# M_microcontrolador.net
KiCad netlist of a schematic drawn in Altium Designer
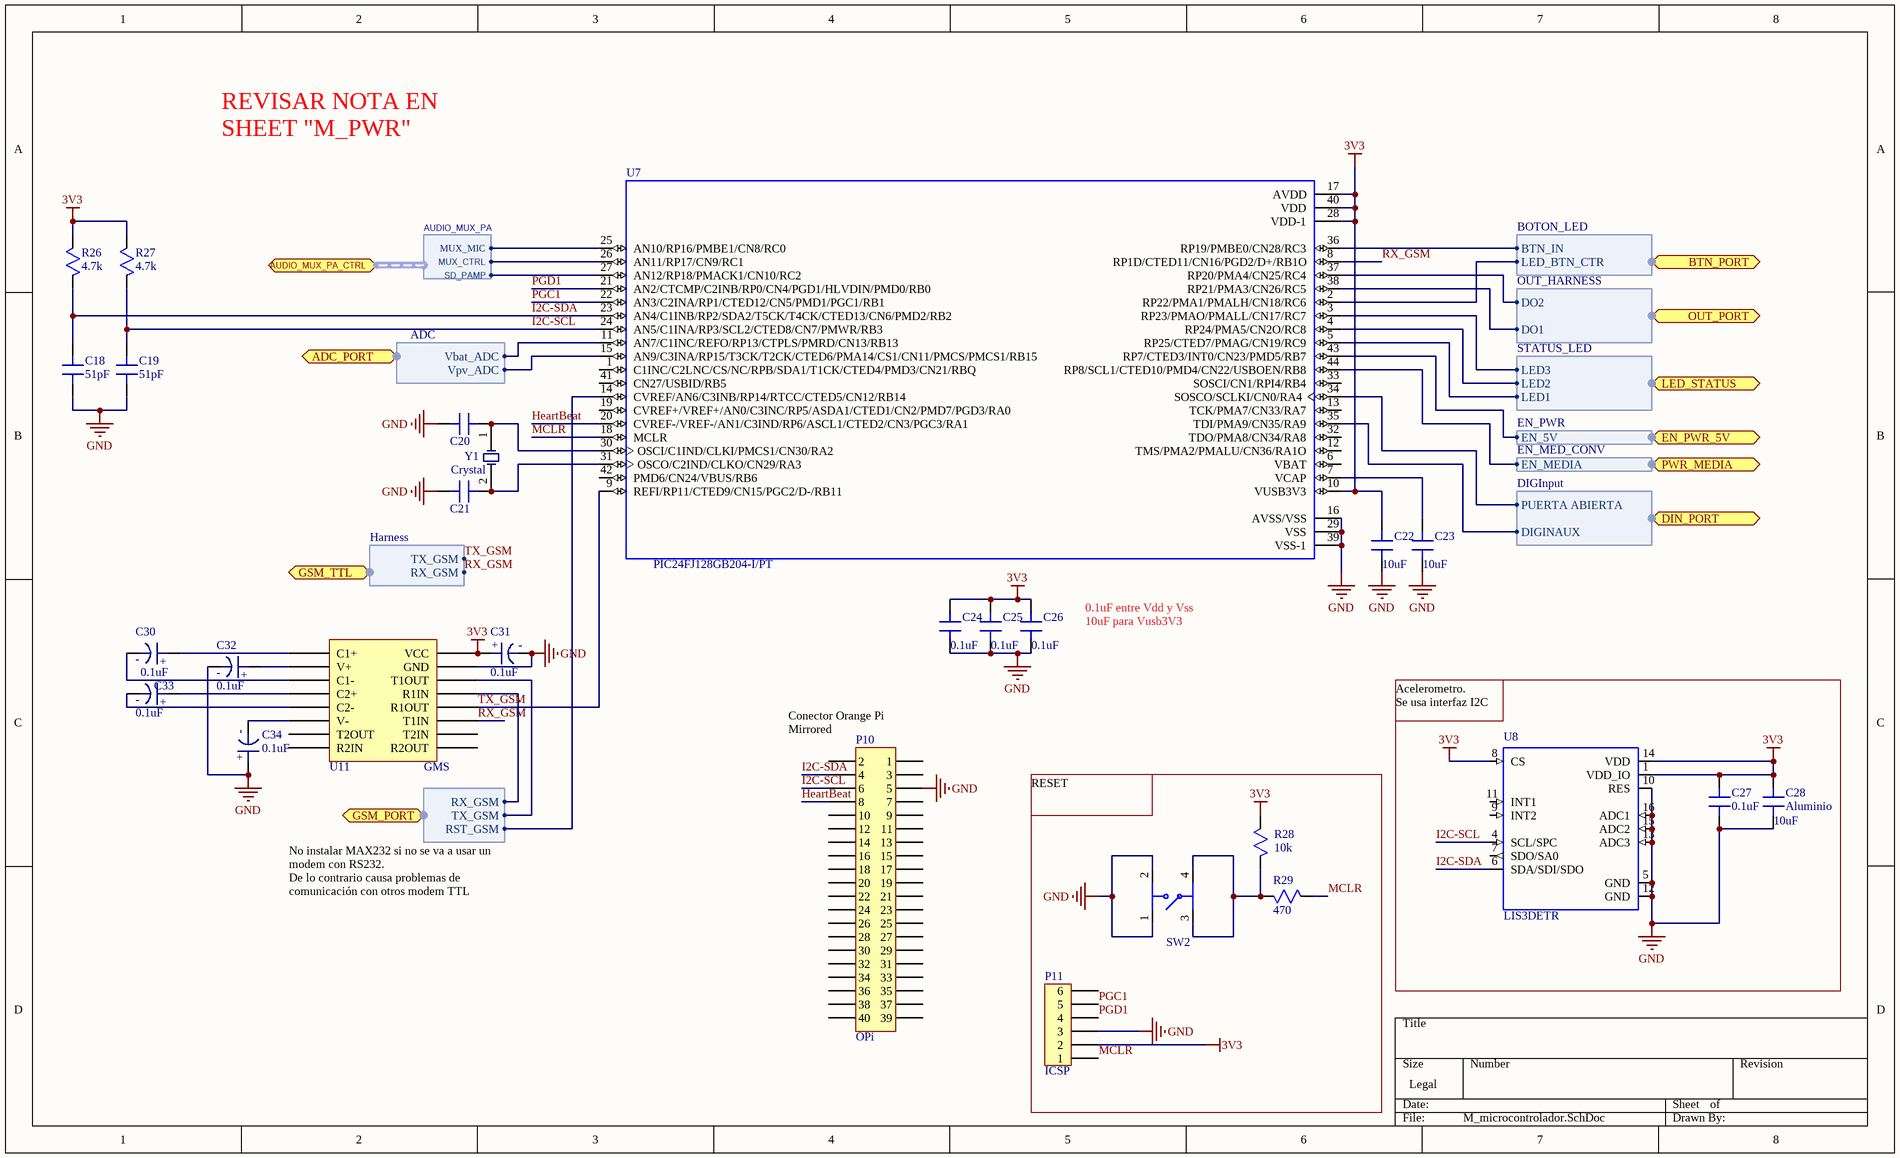
[diagram p0: M_microcontrolador.SchDoc]

(export (version "E")
  (design (tool "Eeschema 10.0.6"))
  (components
    (comp (ref "C18")
      (value "51pF")
      (footprint "Capacitor0805")
      (description "Ceramic Capacitor")
      (fields
        (field (name "DIGI-KEY PART NUMBER") "1276-2670-1-ND")
        (field (name "PARTNO") "CL21C510JBANNNC")
      )
      (libsource (lib "PAT_Library") (part "CapacitorSMD"))
    )
    (comp (ref "C19")
      (value "51pF")
      (footprint "Capacitor0805")
      (description "Ceramic Capacitor")
      (fields
        (field (name "DIGI-KEY PART NUMBER") "1276-2670-1-ND")
        (field (name "PARTNO") "CL21C510JBANNNC")
      )
      (libsource (lib "PAT_Library") (part "CapacitorSMD"))
    )
    (comp (ref "C20")
      (value "CapacitorSMD")
      (footprint "Capacitor0805")
      (description "Ceramic Capacitor")
      (fields (field (name "DIGI-KEY PART NUMBER") "478-10411-1-ND") (field (name "PARTNO") "08051A6R0CAT2A"))
      (libsource (lib "PAT_Library") (part "CapacitorSMD"))
    )
    (comp (ref "C21")
      (value "CapacitorSMD")
      (footprint "Capacitor0805")
      (description "Ceramic Capacitor")
      (fields (field (name "DIGI-KEY PART NUMBER") "478-10411-1-ND") (field (name "PARTNO") "08051A6R0CAT2A"))
      (libsource (lib "PAT_Library") (part "CapacitorSMD"))
    )
    (comp (ref "C22")
      (value "10uF")
      (footprint "Capacitor0805")
      (description "Ceramic Capacitor")
      (fields
        (field (name "DIGI-KEY PART NUMBER") "311-1355-1-ND")
        (field (name "PARTNO") "CC0805ZKY5V6BB106")
      )
      (libsource (lib "ComponentesTruffaV2") (part "CapacitorSMD"))
    )
    (comp (ref "C23")
      (value "10uF")
      (footprint "Capacitor0805")
      (description "Ceramic Capacitor")
      (fields
        (field (name "DIGI-KEY PART NUMBER") "311-1355-1-ND")
        (field (name "PARTNO") "CC0805ZKY5V6BB106")
      )
      (libsource (lib "ComponentesTruffaV2") (part "CapacitorSMD"))
    )
    (comp (ref "C24")
      (value "0.1uF")
      (footprint "Capacitor0805")
      (description "Ceramic Capacitor")
      (fields
        (field (name "DIGI-KEY PART NUMBER") "311-1141-1-ND")
        (field (name "PARTNO") "CC0805KRX7R8BB104")
      )
      (libsource (lib "ComponentesTruffaV2") (part "CapacitorSMD"))
    )
    (comp (ref "C25")
      (value "0.1uF")
      (footprint "Capacitor0805")
      (description "Ceramic Capacitor")
      (fields
        (field (name "DIGI-KEY PART NUMBER") "311-1141-1-ND")
        (field (name "PARTNO") "CC0805KRX7R8BB104")
      )
      (libsource (lib "ComponentesTruffaV2") (part "CapacitorSMD"))
    )
    (comp (ref "C26")
      (value "0.1uF")
      (footprint "Capacitor0805")
      (description "Ceramic Capacitor")
      (fields
        (field (name "DIGI-KEY PART NUMBER") "311-1141-1-ND")
        (field (name "PARTNO") "CC0805KRX7R8BB104")
      )
      (libsource (lib "ComponentesTruffaV2") (part "CapacitorSMD"))
    )
    (comp (ref "C27")
      (value "0.1uF")
      (footprint "Capacitor0805")
      (description "Ceramic Capacitor")
      (fields
        (field (name "DIGI-KEY PART NUMBER") "311-1141-1-ND")
        (field (name "PARTNO") "CC0805KRX7R8BB104")
      )
      (libsource (lib "ComponentesTruffaV2") (part "CapacitorSMD"))
    )
    (comp (ref "C28")
      (value "Aluminio")
      (footprint "Capacitor0805")
      (description "Ceramic Capacitor")
      (fields
        (field (name "ALTIUM_VALUE") "10uF")
        (field (name "DIGI-KEY PART NUMBER") "311-1355-1-ND")
        (field (name "PARTNO") "CC0805ZKY5V6BB106")
      )
      (libsource (lib "ComponentesTruffaV2") (part "CapacitorSMD"))
    )
    (comp (ref "C30")
      (value "0.1uF")
      (footprint "CAPACITORE0805")
      (description "Electrolitic Capacitor")
      (fields
        (field (name "DIGI-KEY PART NUMBER") "311-1141-1-ND")
        (field (name "PARTNO") "CC0805KRX7R8BB104")
      )
      (libsource (lib "PAT_Library") (part "CapacitorESMD"))
    )
    (comp (ref "C31")
      (value "0.1uF")
      (footprint "CAPACITORE0805")
      (description "Electrolitic Capacitor")
      (fields
        (field (name "DIGI-KEY PART NUMBER") "311-1141-1-ND")
        (field (name "PARTNO") "CC0805KRX7R8BB104")
      )
      (libsource (lib "PAT_Library") (part "CapacitorESMD"))
    )
    (comp (ref "C32")
      (value "0.1uF")
      (footprint "CAPACITORE0805")
      (description "Electrolitic Capacitor")
      (fields
        (field (name "DIGI-KEY PART NUMBER") "311-1141-1-ND")
        (field (name "PARTNO") "CC0805KRX7R8BB104")
      )
      (libsource (lib "PAT_Library") (part "CapacitorESMD"))
    )
    (comp (ref "C33")
      (value "0.1uF")
      (footprint "CAPACITORE0805")
      (description "Electrolitic Capacitor")
      (fields
        (field (name "DIGI-KEY PART NUMBER") "311-1141-1-ND")
        (field (name "PARTNO") "CC0805KRX7R8BB104")
      )
      (libsource (lib "PAT_Library") (part "CapacitorESMD"))
    )
    (comp (ref "C34")
      (value "0.1uF")
      (footprint "CAPACITORE0805")
      (description "Electrolitic Capacitor")
      (fields
        (field (name "DIGI-KEY PART NUMBER") "311-1141-1-ND")
        (field (name "PARTNO") "CC0805KRX7R8BB104")
      )
      (libsource (lib "") (part "CapacitorESMD_1"))
    )
    (comp (ref "P10")
      (value "OPi")
      (footprint "MALE2x20PIN")
      (description "Pin Header Male 40 Pins Pitch 2.54mm")
      (fields
        (field (name "DIGI-KEY PART NUMBER") "S7123-ND")
        (field (name "PARTNO") "CONN HDR 40POS 0.1 GOLD PCB")
      )
      (libsource (lib "PAT Connectors Board") (part "PHM2x20P2.54"))
    )
    (comp (ref "P11")
      (value "ICSP")
      (footprint "MALE6PIN")
      (description "Pin Header Male 6 Pins Pitch 2.54mm")
      (fields
        (field (name "DIGI-KEY PART NUMBER") "952-2247-ND")
        (field (name "PARTNO") "CONN HEADER R/A 6POS 2.54MM")
      )
      (libsource (lib "PAT Connectors Board") (part "PHM1x6P2.54"))
    )
    (comp (ref "R26")
      (value "4.7k")
      (footprint "ResistorSMD0805")
      (description "Chip Resistor SMD")
      (fields
        (field (name "DIGI-KEY PART NUMBER") "P4.7KACT-ND")
        (field (name "MANUFACTURERS PART NUMBER") "ERJ-6GEYJ472V")
      )
      (libsource (lib "PAT_Library") (part "ResistorSMD"))
    )
    (comp (ref "R27")
      (value "4.7k")
      (footprint "ResistorSMD0805")
      (description "Chip Resistor SMD")
      (fields
        (field (name "DIGI-KEY PART NUMBER") "P4.7KACT-ND")
        (field (name "MANUFACTURERS PART NUMBER") "ERJ-6GEYJ472V")
      )
      (libsource (lib "PAT_Library") (part "ResistorSMD"))
    )
    (comp (ref "R28")
      (value "10k")
      (footprint "ResistorSMD0805")
      (description "Chip Resistor SMD")
      (fields
        (field (name "DIGI-KEY PART NUMBER") "311-10KARCT-ND")
        (field (name "MANUFACTURERS PART NUMBER") "RC0805JR-0710KL")
      )
      (libsource (lib "PAT_Library") (part "ResistorSMD"))
    )
    (comp (ref "R29")
      (value "470")
      (footprint "ResistorSMD1206")
      (description "Chip Resistor SMD")
      (fields
        (field (name "DIGI-KEY PART NUMBER") "1276-5903-1-ND")
        (field (name "MANUFACTURERS PART NUMBER") "RC3216J471CS")
      )
      (libsource (lib "PAT_Library") (part "ResistorSMD"))
    )
    (comp (ref "SW2")
      (value "Tactile Switch")
      (footprint "TactileSwitch")
      (description "Switch Contact")
      (fields
        (field (name "DIGI-KEY PART NUMBER") "CKN9112CT-ND")
        (field (name "MANUFACTURERS PART NUMBER") "PTS645SM43SMTR92 LFS")
      )
      (libsource (lib "PAT_Library") (part "Tactile Switch"))
    )
    (comp (ref "U7")
      (value "PIC24FJ128GB204-I/PT")
      (footprint "QFP80P1200X1200X120-44N")
      (description "128KB Flash, 8KB RAM, 16 MIPS, USB OTG, Crypto, 44 TQFP 10x10x1mm TRAY")
      (fields (field (name "DIGI-KEY PART NUMBER") "PIC24FJ128GB204-I/PT-ND"))
      (libsource (lib "PIC24FJ128GB204-I_PT") (part "PIC24FJ128GB204-I/PT"))
    )
    (comp (ref "U8")
      (value "LIS3DETR")
      (footprint "LGA16R50P5X3_300X300X100N")
      (description "MEMS digital output motion sensor ultra low-power high performance 3-axes nano accelerometer")
      (fields (field (name "DIGI-KEY PART NUMBER") "497-16262-1-ND"))
      (libsource (lib "LIS3DETR") (part "LIS3DETR"))
    )
    (comp (ref "U11")
      (value "SP3232EBCN")
      (footprint "SP3232EBCN")
      (description "Serial Adapter RS232")
      (fields
        (field (name "DIGI-KEY PART NUMBER") "1016-1803-1-ND")
        (field (name "MANUFACTURERS PART NUMBER") "SP3232ECN-L/TR")
      )
      (libsource (lib "PAT_Library") (part "SP3232EBCN"))
    )
    (comp (ref "Y1")
      (value "Crystal")
      (footprint "CRYSTALSMDMini")
      (description "Crystal SMD")
      (fields
        (field (name "DIGI-KEY PART NUMBER") "XC1842CT-ND")
        (field (name "MANUFACTURERS PART NUMBER") "ECS-240-8-30B-CKM")
      )
      (libsource (lib "PAT_Library") (part "Crystal"))
    )
  )
  (nets
    (net (code "11") (name "/BTN_IN") (class "Default")
      (node (ref "U7") (pin "36") (pinfunction "RP19/PMBE0/CN28/RC3_36") (pintype "bidirectional"))
    )
    (net (code "12") (name "/DIGINAUX") (class "Default")
      (node (ref "U7") (pin "35") (pinfunction "TDI/PMA9/CN35/RA9_35") (pintype "bidirectional"))
    )
    (net (code "13") (name "/DO1") (class "Default")
      (node (ref "U7") (pin "38") (pinfunction "RP21/PMA3/CN26/RC5_38") (pintype "bidirectional"))
    )
    (net (code "14") (name "/DO2") (class "Default")
      (node (ref "U7") (pin "37") (pinfunction "RP20/PMA4/CN25/RC4_37") (pintype "bidirectional"))
    )
    (net (code "15") (name "/EN_5V") (class "Default")
      (node (ref "U7") (pin "43") (pinfunction "RP7/CTED3/INT0/CN23/PMD5/RB7_43") (pintype "bidirectional"))
    )
    (net (code "16") (name "/EN_MEDIA") (class "Default")
      (node (ref "U7") (pin "44") (pinfunction "RP8/SCL1/CTED10/PMD4/CN22/USBOEN/RB8_44") (pintype "bidirectional"))
    )
    (net (code "17") (name "/HeartBeat") (class "Default")
      (node (ref "P10") (pin "8") (pinfunction "8_8") (pintype "passive"))
      (node (ref "U7") (pin "20") (pinfunction "CVREF-/VREF-/AN1/C3IND/RP6/ASCL1/CTED2/CN3/PGC3/RA1_20") (pintype "bidirectional"))
    )
    (net (code "18") (name "/I2C-SCL") (class "Default")
      (node (ref "C19") (pin "1") (pinfunction "1_1") (pintype "passive"))
      (node (ref "P10") (pin "6") (pinfunction "6_6") (pintype "passive"))
      (node (ref "R27") (pin "1") (pinfunction "1_1") (pintype "passive"))
      (node (ref "U7") (pin "24") (pinfunction "AN5/C1INA/RP3/SCL2/CTED8/CN7/PMWR/RB3_24") (pintype "bidirectional"))
      (node (ref "U8") (pin "4") (pinfunction "SCL/SPC_4") (pintype "input"))
    )
    (net (code "19") (name "/I2C-SDA") (class "Default")
      (node (ref "C18") (pin "1") (pinfunction "1_1") (pintype "passive"))
      (node (ref "P10") (pin "4") (pinfunction "4_4") (pintype "passive"))
      (node (ref "R26") (pin "1") (pinfunction "1_1") (pintype "passive"))
      (node (ref "U7") (pin "23") (pinfunction "AN4/C1INB/RP2/SDA2/T5CK/T4CK/CTED13/CN6/PMD2/RB2_23") (pintype "bidirectional"))
      (node (ref "U8") (pin "6") (pinfunction "SDA/SDI/SDO_6") (pintype "bidirectional"))
    )
    (net (code "20") (name "/LED1") (class "Default")
      (node (ref "U7") (pin "5") (pinfunction "RP25/CTED7/PMAG/CN19/RC9_5") (pintype "bidirectional"))
    )
    (net (code "21") (name "/LED2") (class "Default")
      (node (ref "U7") (pin "4") (pinfunction "RP24/PMA5/CN2O/RC8_4") (pintype "bidirectional"))
    )
    (net (code "22") (name "/LED3") (class "Default")
      (node (ref "U7") (pin "3") (pinfunction "RP23/PMAO/PMALL/CN17/RC7_3") (pintype "bidirectional"))
    )
    (net (code "23") (name "/LED_BTN_CTR") (class "Default")
      (node (ref "U7") (pin "2") (pinfunction "RP22/PMA1/PMALH/CN18/RC6_2") (pintype "bidirectional"))
    )
    (net (code "24") (name "/MCLR") (class "Default")
      (node (ref "P11") (pin "1") (pinfunction "1_1") (pintype "passive"))
      (node (ref "R29") (pin "2") (pinfunction "2_2") (pintype "passive"))
      (node (ref "U7") (pin "18") (pinfunction "MCLR_18") (pintype "bidirectional"))
    )
    (net (code "25") (name "/MUX_CTRL") (class "Default")
      (node (ref "U7") (pin "26") (pinfunction "AN11/RP17/CN9/RC1_26") (pintype "bidirectional"))
    )
    (net (code "26") (name "/MUX_MIC") (class "Default")
      (node (ref "U7") (pin "25") (pinfunction "AN10/RP16/PMBE1/CN8/RC0_25") (pintype "bidirectional"))
    )
    (net (code "27") (name "/PGC1") (class "Default")
      (node (ref "P11") (pin "5") (pinfunction "5_5") (pintype "passive"))
      (node (ref "U7") (pin "22") (pinfunction "AN3/C2INA/RP1/CTED12/CN5/PMD1/PGC1/RB1_22") (pintype "bidirectional"))
    )
    (net (code "28") (name "/PGD1") (class "Default")
      (node (ref "P11") (pin "4") (pinfunction "4_4") (pintype "passive"))
      (node (ref "U7") (pin "21") (pinfunction "AN2/CTCMP/C2INB/RP0/CN4/PGD1/HLVDIN/PMD0/RB0_21") (pintype "bidirectional"))
    )
    (net (code "29") (name "/PUERTA ABIERTA") (class "Default")
      (node (ref "U7") (pin "34") (pinfunction "SOSCO/SCLKI/CN0/RA4_34") (pintype "bidirectional"))
    )
    (net (code "30") (name "/RST_GSM") (class "Default")
      (node (ref "U7") (pin "14") (pinfunction "CVREF/AN6/C3INB/RP14/RTCC/CTED5/CN12/RB14_14") (pintype "bidirectional"))
    )
    (net (code "31") (name "/RX_GSM") (class "Default")
      (node (ref "U11") (pin "11") (pinfunction "T1IN_11") (pintype "passive"))
      (node (ref "U7") (pin "8") (pinfunction "RP1D/CTED11/CN16/PGD2/D+/RB1O_8") (pintype "bidirectional"))
    )
    (net (code "32") (name "/SD_PAMP") (class "Default")
      (node (ref "U7") (pin "27") (pinfunction "AN12/RP18/PMACK1/CN10/RC2_27") (pintype "bidirectional"))
    )
    (net (code "33") (name "/TX_GSM") (class "Default")
      (node (ref "U11") (pin "12") (pinfunction "R1OUT_12") (pintype "passive"))
      (node (ref "U7") (pin "9") (pinfunction "REFI/RP11/CTED9/CN15/PGC2/D-/RB11_9") (pintype "bidirectional"))
    )
    (net (code "34") (name "/Vbat_ADC") (class "Default")
      (node (ref "U7") (pin "11") (pinfunction "AN7/C1INC/REFO/RP13/CTPLS/PMRD/CN13/RB13_11") (pintype "bidirectional"))
    )
    (net (code "35") (name "/Vpv_ADC") (class "Default")
      (node (ref "U7") (pin "15") (pinfunction "AN9/C3INA/RP15/T3CK/T2CK/CTED6/PMA14/CS1/CN11/PMCS/PMCS1/RB15_15") (pintype "bidirectional"))
    )
    (net (code "46") (name "3V3") (class "Default")
      (node (ref "C22") (pin "2") (pinfunction "2_2") (pintype "passive"))
      (node (ref "C24") (pin "2") (pinfunction "2_2") (pintype "passive"))
      (node (ref "C25") (pin "2") (pinfunction "2_2") (pintype "passive"))
      (node (ref "C26") (pin "2") (pinfunction "2_2") (pintype "passive"))
      (node (ref "C27") (pin "2") (pinfunction "2_2") (pintype "passive"))
      (node (ref "C28") (pin "2") (pinfunction "2_2") (pintype "passive"))
      (node (ref "C31") (pin "1") (pinfunction "1_1") (pintype "passive"))
      (node (ref "P11") (pin "2") (pinfunction "2_2") (pintype "passive"))
      (node (ref "R26") (pin "2") (pinfunction "2_2") (pintype "passive"))
      (node (ref "R27") (pin "2") (pinfunction "2_2") (pintype "passive"))
      (node (ref "R28") (pin "2") (pinfunction "2_2") (pintype "passive"))
      (node (ref "U11") (pin "16") (pinfunction "VCC_16") (pintype "passive"))
      (node (ref "U7") (pin "10") (pinfunction "VUSB3V3_10") (pintype "bidirectional"))
      (node (ref "U7") (pin "17") (pinfunction "AVDD_17") (pintype "power_in"))
      (node (ref "U7") (pin "28") (pinfunction "VDD-1_28") (pintype "power_in"))
      (node (ref "U7") (pin "40") (pinfunction "VDD_40") (pintype "power_in"))
      (node (ref "U8") (pin "1") (pinfunction "VDD_IO_1") (pintype "power_in"))
      (node (ref "U8") (pin "14") (pinfunction "VDD_14") (pintype "power_in"))
      (node (ref "U8") (pin "8") (pinfunction "CS_8") (pintype "input"))
    )
    (net (code "47") (name "GND") (class "Default")
      (node (ref "C18") (pin "2") (pinfunction "2_2") (pintype "passive"))
      (node (ref "C19") (pin "2") (pinfunction "2_2") (pintype "passive"))
      (node (ref "C20") (pin "1") (pinfunction "1_1") (pintype "passive"))
      (node (ref "C21") (pin "1") (pinfunction "1_1") (pintype "passive"))
      (node (ref "C22") (pin "1") (pinfunction "1_1") (pintype "passive"))
      (node (ref "C23") (pin "1") (pinfunction "1_1") (pintype "passive"))
      (node (ref "C24") (pin "1") (pinfunction "1_1") (pintype "passive"))
      (node (ref "C25") (pin "1") (pinfunction "1_1") (pintype "passive"))
      (node (ref "C26") (pin "1") (pinfunction "1_1") (pintype "passive"))
      (node (ref "C27") (pin "1") (pinfunction "1_1") (pintype "passive"))
      (node (ref "C28") (pin "1") (pinfunction "1_1") (pintype "passive"))
      (node (ref "C31") (pin "2") (pinfunction "2_2") (pintype "passive"))
      (node (ref "C32") (pin "2") (pinfunction "2_2") (pintype "passive"))
      (node (ref "C34") (pin "1") (pinfunction "1_1") (pintype "passive"))
      (node (ref "P10") (pin "5") (pinfunction "5_5") (pintype "passive"))
      (node (ref "P11") (pin "3") (pinfunction "3_3") (pintype "passive"))
      (node (ref "SW2") (pin "1") (pinfunction "1_1") (pintype "passive"))
      (node (ref "SW2") (pin "2") (pinfunction "2_2") (pintype "passive"))
      (node (ref "U11") (pin "15") (pinfunction "GND_15") (pintype "passive"))
      (node (ref "U7") (pin "16") (pinfunction "AVSS/VSS_16") (pintype "power_in"))
      (node (ref "U7") (pin "29") (pinfunction "VSS_29") (pintype "power_in"))
      (node (ref "U7") (pin "39") (pinfunction "VSS-1_39") (pintype "power_in"))
      (node (ref "U8") (pin "10") (pinfunction "RES_10") (pintype "power_in"))
      (node (ref "U8") (pin "12") (pinfunction "GND_12") (pintype "power_in"))
      (node (ref "U8") (pin "13") (pinfunction "ADC3_13") (pintype "input"))
      (node (ref "U8") (pin "15") (pinfunction "ADC2_15") (pintype "input"))
      (node (ref "U8") (pin "16") (pinfunction "ADC1_16") (pintype "input"))
      (node (ref "U8") (pin "5") (pinfunction "GND_5") (pintype "power_in"))
    )
    (net (code "48") (name "Net-(R28-Pad1)") (class "Default")
      (node (ref "R28") (pin "1") (pinfunction "1_1") (pintype "passive"))
      (node (ref "R29") (pin "1") (pinfunction "1_1") (pintype "passive"))
      (node (ref "SW2") (pin "3") (pinfunction "3_3") (pintype "passive"))
      (node (ref "SW2") (pin "4") (pinfunction "4_4") (pintype "passive"))
    )
    (net (code "49") (name "Net-(U7-OSCI{slash}C1IND{slash}CLKI{slash}PMCS1{slash}CN30{slash}RA2)") (class "Default")
      (node (ref "C20") (pin "2") (pinfunction "2_2") (pintype "passive"))
      (node (ref "U7") (pin "30") (pinfunction "OSCI/C1IND/CLKI/PMCS1/CN30/RA2_30") (pintype "bidirectional"))
      (node (ref "Y1") (pin "1") (pinfunction "1_1") (pintype "passive"))
    )
    (net (code "50") (name "Net-(U7-OSCO{slash}C2IND{slash}CLKO{slash}CN29{slash}RA3)") (class "Default")
      (node (ref "C21") (pin "2") (pinfunction "2_2") (pintype "passive"))
      (node (ref "U7") (pin "31") (pinfunction "OSCO/C2IND/CLKO/CN29/RA3_31") (pintype "bidirectional"))
      (node (ref "Y1") (pin "2") (pinfunction "2_2") (pintype "passive"))
    )
    (net (code "51") (name "Net-(U7-VCAP)") (class "Default")
      (node (ref "C23") (pin "2") (pinfunction "2_2") (pintype "passive"))
      (node (ref "U7") (pin "7") (pinfunction "VCAP_7") (pintype "bidirectional"))
    )
    (net (code "52") (name "Net-(U11-C1+)") (class "Default")
      (node (ref "C30") (pin "1") (pinfunction "1_1") (pintype "passive"))
      (node (ref "U11") (pin "1") (pinfunction "C1+_1") (pintype "passive"))
    )
    (net (code "53") (name "Net-(U11-C1-)") (class "Default")
      (node (ref "C30") (pin "2") (pinfunction "2_2") (pintype "passive"))
      (node (ref "U11") (pin "3") (pinfunction "C1-_3") (pintype "passive"))
    )
    (net (code "54") (name "Net-(U11-C2+)") (class "Default")
      (node (ref "C33") (pin "1") (pinfunction "1_1") (pintype "passive"))
      (node (ref "U11") (pin "4") (pinfunction "C2+_4") (pintype "passive"))
    )
    (net (code "55") (name "Net-(U11-C2-)") (class "Default")
      (node (ref "C33") (pin "2") (pinfunction "2_2") (pintype "passive"))
      (node (ref "U11") (pin "5") (pinfunction "C2-_5") (pintype "passive"))
    )
    (net (code "56") (name "Net-(U11-V+)") (class "Default")
      (node (ref "C32") (pin "1") (pinfunction "1_1") (pintype "passive"))
      (node (ref "U11") (pin "2") (pinfunction "V+_2") (pintype "passive"))
    )
    (net (code "57") (name "Net-(U11-V-)") (class "Default")
      (node (ref "C34") (pin "2") (pinfunction "2_2") (pintype "passive"))
      (node (ref "U11") (pin "6") (pinfunction "V-_6") (pintype "passive"))
    )
    (net (code "58") (name "unconnected-(P10-Pad1)") (class "Default")
      (node (ref "P10") (pin "1") (pinfunction "1_1") (pintype "passive"))
    )
    (net (code "59") (name "unconnected-(P10-Pad2)") (class "Default")
      (node (ref "P10") (pin "2") (pinfunction "2_2") (pintype "passive"))
    )
    (net (code "60") (name "unconnected-(P10-Pad3)") (class "Default")
      (node (ref "P10") (pin "3") (pinfunction "3_3") (pintype "passive"))
    )
    (net (code "61") (name "unconnected-(P10-Pad7)") (class "Default")
      (node (ref "P10") (pin "7") (pinfunction "7_7") (pintype "passive"))
    )
    (net (code "62") (name "unconnected-(P10-Pad9)") (class "Default")
      (node (ref "P10") (pin "9") (pinfunction "9_9") (pintype "passive"))
    )
    (net (code "63") (name "unconnected-(P10-Pad10)") (class "Default")
      (node (ref "P10") (pin "10") (pinfunction "10_10") (pintype "passive"))
    )
    (net (code "64") (name "unconnected-(P10-Pad11)") (class "Default")
      (node (ref "P10") (pin "11") (pinfunction "11_11") (pintype "passive"))
    )
    (net (code "65") (name "unconnected-(P10-Pad12)") (class "Default")
      (node (ref "P10") (pin "12") (pinfunction "12_12") (pintype "passive"))
    )
    (net (code "66") (name "unconnected-(P10-Pad13)") (class "Default")
      (node (ref "P10") (pin "13") (pinfunction "13_13") (pintype "passive"))
    )
    (net (code "67") (name "unconnected-(P10-Pad14)") (class "Default")
      (node (ref "P10") (pin "14") (pinfunction "14_14") (pintype "passive"))
    )
    (net (code "68") (name "unconnected-(P10-Pad15)") (class "Default")
      (node (ref "P10") (pin "15") (pinfunction "15_15") (pintype "passive"))
    )
    (net (code "69") (name "unconnected-(P10-Pad16)") (class "Default")
      (node (ref "P10") (pin "16") (pinfunction "16_16") (pintype "passive"))
    )
    (net (code "70") (name "unconnected-(P10-Pad17)") (class "Default")
      (node (ref "P10") (pin "17") (pinfunction "17_17") (pintype "passive"))
    )
    (net (code "71") (name "unconnected-(P10-Pad18)") (class "Default")
      (node (ref "P10") (pin "18") (pinfunction "18_18") (pintype "passive"))
    )
    (net (code "72") (name "unconnected-(P10-Pad19)") (class "Default")
      (node (ref "P10") (pin "19") (pinfunction "19_19") (pintype "passive"))
    )
    (net (code "73") (name "unconnected-(P10-Pad20)") (class "Default")
      (node (ref "P10") (pin "20") (pinfunction "20_20") (pintype "passive"))
    )
    (net (code "74") (name "unconnected-(P10-Pad21)") (class "Default")
      (node (ref "P10") (pin "21") (pinfunction "21_21") (pintype "passive"))
    )
    (net (code "75") (name "unconnected-(P10-Pad22)") (class "Default")
      (node (ref "P10") (pin "22") (pinfunction "22_22") (pintype "passive"))
    )
    (net (code "76") (name "unconnected-(P10-Pad23)") (class "Default")
      (node (ref "P10") (pin "23") (pinfunction "23_23") (pintype "passive"))
    )
    (net (code "77") (name "unconnected-(P10-Pad24)") (class "Default")
      (node (ref "P10") (pin "24") (pinfunction "24_24") (pintype "passive"))
    )
    (net (code "78") (name "unconnected-(P10-Pad25)") (class "Default")
      (node (ref "P10") (pin "25") (pinfunction "25_25") (pintype "passive"))
    )
    (net (code "79") (name "unconnected-(P10-Pad26)") (class "Default")
      (node (ref "P10") (pin "26") (pinfunction "26_26") (pintype "passive"))
    )
    (net (code "80") (name "unconnected-(P10-Pad27)") (class "Default")
      (node (ref "P10") (pin "27") (pinfunction "27_27") (pintype "passive"))
    )
    (net (code "81") (name "unconnected-(P10-Pad28)") (class "Default")
      (node (ref "P10") (pin "28") (pinfunction "28_28") (pintype "passive"))
    )
    (net (code "82") (name "unconnected-(P10-Pad29)") (class "Default")
      (node (ref "P10") (pin "29") (pinfunction "29_29") (pintype "passive"))
    )
    (net (code "83") (name "unconnected-(P10-Pad30)") (class "Default")
      (node (ref "P10") (pin "30") (pinfunction "30_30") (pintype "passive"))
    )
    (net (code "84") (name "unconnected-(P10-Pad31)") (class "Default")
      (node (ref "P10") (pin "31") (pinfunction "31_31") (pintype "passive"))
    )
    (net (code "85") (name "unconnected-(P10-Pad32)") (class "Default")
      (node (ref "P10") (pin "32") (pinfunction "32_32") (pintype "passive"))
    )
    (net (code "86") (name "unconnected-(P10-Pad33)") (class "Default")
      (node (ref "P10") (pin "33") (pinfunction "33_33") (pintype "passive"))
    )
    (net (code "87") (name "unconnected-(P10-Pad34)") (class "Default")
      (node (ref "P10") (pin "34") (pinfunction "34_34") (pintype "passive"))
    )
    (net (code "88") (name "unconnected-(P10-Pad35)") (class "Default")
      (node (ref "P10") (pin "35") (pinfunction "35_35") (pintype "passive"))
    )
    (net (code "89") (name "unconnected-(P10-Pad36)") (class "Default")
      (node (ref "P10") (pin "36") (pinfunction "36_36") (pintype "passive"))
    )
    (net (code "90") (name "unconnected-(P10-Pad37)") (class "Default")
      (node (ref "P10") (pin "37") (pinfunction "37_37") (pintype "passive"))
    )
    (net (code "91") (name "unconnected-(P10-Pad38)") (class "Default")
      (node (ref "P10") (pin "38") (pinfunction "38_38") (pintype "passive"))
    )
    (net (code "92") (name "unconnected-(P10-Pad39)") (class "Default")
      (node (ref "P10") (pin "39") (pinfunction "39_39") (pintype "passive"))
    )
    (net (code "93") (name "unconnected-(P10-Pad40)") (class "Default")
      (node (ref "P10") (pin "40") (pinfunction "40_40") (pintype "passive"))
    )
    (net (code "94") (name "unconnected-(P11-Pad6)") (class "Default")
      (node (ref "P11") (pin "6") (pinfunction "6_6") (pintype "passive"))
    )
    (net (code "95") (name "unconnected-(U7-C1INC{slash}C2LNC{slash}CS{slash}NC{slash}RPB{slash}SDA1{slash}T1CK{slash}CTED4{slash}PMD3{slash}CN21{slash}RBQ-Pad1)") (class "Default")
      (node (ref "U7") (pin "1") (pinfunction "C1INC/C2LNC/CS/NC/RPB/SDA1/T1CK/CTED4/PMD3/CN21/RBQ_1") (pintype "bidirectional"))
    )
    (net (code "96") (name "unconnected-(U7-CN27{slash}USBID{slash}RB5-Pad41)") (class "Default")
      (node (ref "U7") (pin "41") (pinfunction "CN27/USBID/RB5_41") (pintype "bidirectional"))
    )
    (net (code "97") (name "unconnected-(U7-CVREF+{slash}VREF+{slash}AN0{slash}C3INC{slash}RP5{slash}ASDA1{slash}CTED1{slash}CN2{slash}PMD7{slash}PGD3{slash}RA0-Pad19)") (class "Default")
      (node (ref "U7") (pin "19") (pinfunction "CVREF+/VREF+/AN0/C3INC/RP5/ASDA1/CTED1/CN2/PMD7/PGD3/RA0_19") (pintype "bidirectional"))
    )
    (net (code "98") (name "unconnected-(U7-PMD6{slash}CN24{slash}VBUS{slash}RB6-Pad42)") (class "Default")
      (node (ref "U7") (pin "42") (pinfunction "PMD6/CN24/VBUS/RB6_42") (pintype "bidirectional"))
    )
    (net (code "99") (name "unconnected-(U7-SOSCI{slash}CN1{slash}RPI4{slash}RB4-Pad33)") (class "Default")
      (node (ref "U7") (pin "33") (pinfunction "SOSCI/CN1/RPI4/RB4_33") (pintype "bidirectional"))
    )
    (net (code "100") (name "unconnected-(U7-TCK{slash}PMA7{slash}CN33{slash}RA7-Pad13)") (class "Default")
      (node (ref "U7") (pin "13") (pinfunction "TCK/PMA7/CN33/RA7_13") (pintype "bidirectional"))
    )
    (net (code "101") (name "unconnected-(U7-TDO{slash}PMA8{slash}CN34{slash}RA8-Pad32)") (class "Default")
      (node (ref "U7") (pin "32") (pinfunction "TDO/PMA8/CN34/RA8_32") (pintype "bidirectional"))
    )
    (net (code "102") (name "unconnected-(U7-TMS{slash}PMA2{slash}PMALU{slash}CN36{slash}RA1O-Pad12)") (class "Default")
      (node (ref "U7") (pin "12") (pinfunction "TMS/PMA2/PMALU/CN36/RA1O_12") (pintype "bidirectional"))
    )
    (net (code "103") (name "unconnected-(U7-VBAT-Pad6)") (class "Default")
      (node (ref "U7") (pin "6") (pinfunction "VBAT_6") (pintype "bidirectional"))
    )
    (net (code "104") (name "unconnected-(U8-INT1-Pad11)") (class "Default")
      (node (ref "U8") (pin "11") (pinfunction "INT1_11") (pintype "input"))
    )
    (net (code "105") (name "unconnected-(U8-INT2-Pad9)") (class "Default")
      (node (ref "U8") (pin "9") (pinfunction "INT2_9") (pintype "input"))
    )
    (net (code "106") (name "unconnected-(U8-SDO{slash}SA0-Pad7)") (class "Default")
      (node (ref "U8") (pin "7") (pinfunction "SDO/SA0_7") (pintype "output"))
    )
    (net (code "107") (name "unconnected-(U11-R1IN-Pad13)") (class "Default")
      (node (ref "U11") (pin "13") (pinfunction "R1IN_13") (pintype "passive"))
    )
    (net (code "108") (name "unconnected-(U11-R2IN-Pad8)") (class "Default")
      (node (ref "U11") (pin "8") (pinfunction "R2IN_8") (pintype "passive"))
    )
    (net (code "109") (name "unconnected-(U11-R2OUT-Pad9)") (class "Default")
      (node (ref "U11") (pin "9") (pinfunction "R2OUT_9") (pintype "passive"))
    )
    (net (code "110") (name "unconnected-(U11-T1OUT-Pad14)") (class "Default")
      (node (ref "U11") (pin "14") (pinfunction "T1OUT_14") (pintype "passive"))
    )
    (net (code "111") (name "unconnected-(U11-T2IN-Pad10)") (class "Default")
      (node (ref "U11") (pin "10") (pinfunction "T2IN_10") (pintype "passive"))
    )
    (net (code "112") (name "unconnected-(U11-T2OUT-Pad7)") (class "Default")
      (node (ref "U11") (pin "7") (pinfunction "T2OUT_7") (pintype "passive"))
    )
  )
)
